# Interconnect_board_limit_switches_v1p5.net
KiCad netlist of a schematic drawn in EAGLE
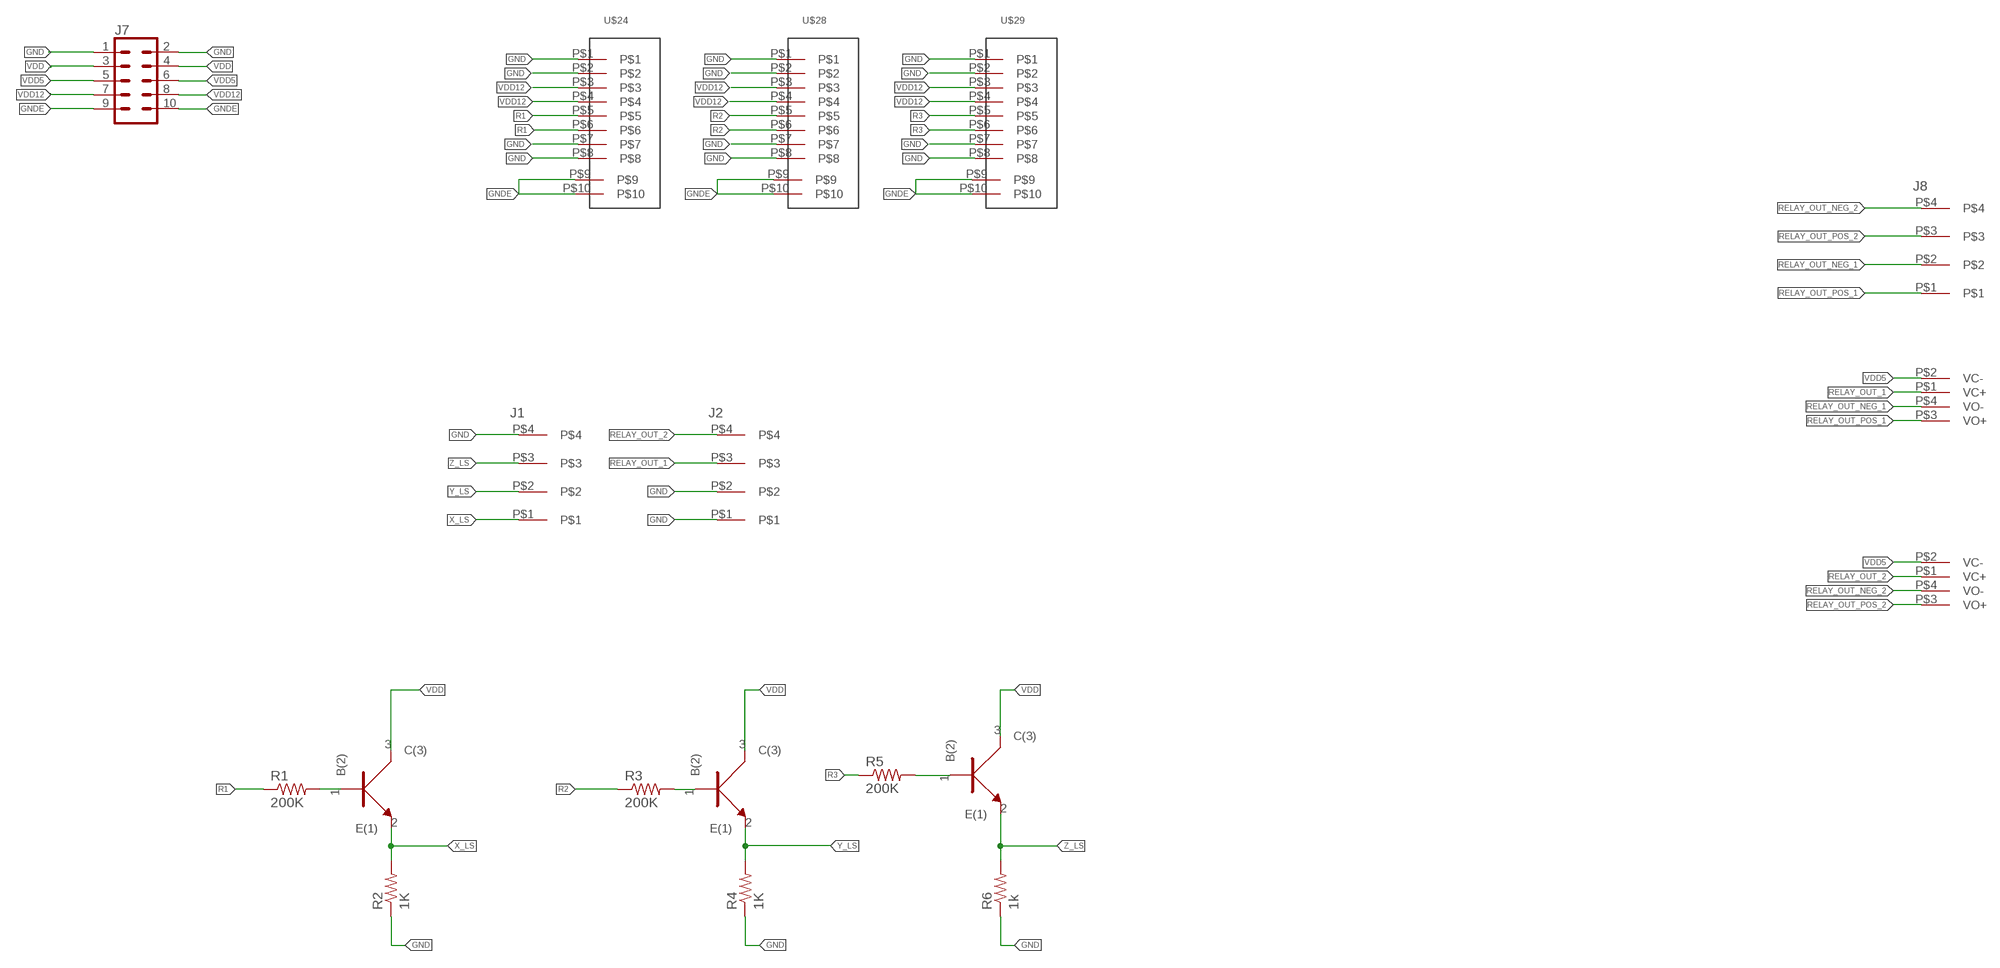
[diagram p0: schematic, sheet 1]

(export (version "E")
  (design (tool "Eeschema 10.0.6"))
  (components
    (comp (ref "J1")
      (value "3.81MM_1_X_4_RT_ANGLE_PLUG_HEADER")
      (footprint "eagle-import:1X4_3.81MM_PITCH")
      (libsource (lib "eagle-import") (part "3.81MM_1_X_4_RT_ANGLE_PLUG_HEADER"))
    )
    (comp (ref "J2")
      (value "3.81MM_1_X_4_RT_ANGLE_PLUG_HEADER")
      (footprint "eagle-import:1X4_3.81MM_PITCH")
      (libsource (lib "eagle-import") (part "3.81MM_1_X_4_RT_ANGLE_PLUG_HEADER"))
    )
    (comp (ref "J7")
      (value "CONN_05X2PTH")
      (footprint "eagle-import:2X5")
      (libsource (lib "eagle-import") (part "CONN_05X2PTH"))
    )
    (comp (ref "J8")
      (value "3.81MM_1_X_4_RT_ANGLE_PLUG_HEADER")
      (footprint "eagle-import:1X4_3.81MM_PITCH")
      (libsource (lib "eagle-import") (part "3.81MM_1_X_4_RT_ANGLE_PLUG_HEADER"))
    )
    (comp (ref "R1")
      (value "200K")
      (footprint "eagle-import:0805")
      (libsource (lib "eagle-import") (part "R_0805"))
    )
    (comp (ref "R2")
      (value "1K")
      (footprint "eagle-import:0805")
      (libsource (lib "eagle-import") (part "R_0805"))
    )
    (comp (ref "R3")
      (value "200K")
      (footprint "eagle-import:0805")
      (libsource (lib "eagle-import") (part "R_0805"))
    )
    (comp (ref "R4")
      (value "1K")
      (footprint "eagle-import:0805")
      (libsource (lib "eagle-import") (part "R_0805"))
    )
    (comp (ref "R5")
      (value "200K")
      (footprint "eagle-import:0805")
      (libsource (lib "eagle-import") (part "R_0805"))
    )
    (comp (ref "R6")
      (value "1k")
      (footprint "eagle-import:0805")
      (libsource (lib "eagle-import") (part "R_0805"))
    )
    (comp (ref "U$5")
      (value "RELAY_KYOTO_KF0604D")
      (footprint "eagle-import:RELAY_KYOTO_KF0604D")
      (libsource (lib "eagle-import") (part "RELAY_KYOTO_KF0604D"))
    )
    (comp (ref "U$13")
      (value "RELAY_KYOTO_KF0604D")
      (footprint "eagle-import:RELAY_KYOTO_KF0604D")
      (libsource (lib "eagle-import") (part "RELAY_KYOTO_KF0604D"))
    )
    (comp (ref "U$24")
      (value "RJ45_SMTRJ")
      (footprint "eagle-import:RJ45_SMT")
      (libsource (lib "eagle-import") (part "RJ45_SMTRJ"))
    )
    (comp (ref "U$28")
      (value "RJ45_SMTRJ")
      (footprint "eagle-import:RJ45_SMT")
      (libsource (lib "eagle-import") (part "RJ45_SMTRJ"))
    )
    (comp (ref "U$29")
      (value "RJ45_SMTRJ")
      (footprint "eagle-import:RJ45_SMT")
      (libsource (lib "eagle-import") (part "RJ45_SMTRJ"))
    )
    (comp (ref "U1")
      (value "BC846BW")
      (footprint "eagle-import:SOT323")
      (libsource (lib "eagle-import") (part "BC846BW"))
    )
    (comp (ref "U2")
      (value "BC846BW")
      (footprint "eagle-import:SOT323")
      (libsource (lib "eagle-import") (part "BC846BW"))
    )
    (comp (ref "U3")
      (value "BC846BW")
      (footprint "eagle-import:SOT323")
      (libsource (lib "eagle-import") (part "BC846BW"))
    )
  )
  (nets
    (net (code "1") (name "GND") (class "Default")
      (node (ref "J1") (pin "P$4") (pinfunction "P$4_P$4") (pintype "bidirectional"))
      (node (ref "J2") (pin "P$1") (pinfunction "P$1_P$1") (pintype "bidirectional"))
      (node (ref "J2") (pin "P$2") (pinfunction "P$2_P$2") (pintype "bidirectional"))
      (node (ref "J7") (pin "1") (pinfunction "1_1") (pintype "passive"))
      (node (ref "J7") (pin "2") (pinfunction "2_2") (pintype "passive"))
      (node (ref "R2") (pin "1") (pinfunction "1_1") (pintype "passive"))
      (node (ref "R4") (pin "1") (pinfunction "1_1") (pintype "passive"))
      (node (ref "R6") (pin "1") (pinfunction "1_1") (pintype "passive"))
      (node (ref "U$24") (pin "P$1") (pinfunction "P$1_P$1") (pintype "bidirectional"))
      (node (ref "U$24") (pin "P$2") (pinfunction "P$2_P$2") (pintype "bidirectional"))
      (node (ref "U$24") (pin "P$7") (pinfunction "P$7_P$7") (pintype "bidirectional"))
      (node (ref "U$24") (pin "P$8") (pinfunction "P$8_P$8") (pintype "bidirectional"))
      (node (ref "U$28") (pin "P$1") (pinfunction "P$1_P$1") (pintype "bidirectional"))
      (node (ref "U$28") (pin "P$2") (pinfunction "P$2_P$2") (pintype "bidirectional"))
      (node (ref "U$28") (pin "P$7") (pinfunction "P$7_P$7") (pintype "bidirectional"))
      (node (ref "U$28") (pin "P$8") (pinfunction "P$8_P$8") (pintype "bidirectional"))
      (node (ref "U$29") (pin "P$1") (pinfunction "P$1_P$1") (pintype "bidirectional"))
      (node (ref "U$29") (pin "P$2") (pinfunction "P$2_P$2") (pintype "bidirectional"))
      (node (ref "U$29") (pin "P$7") (pinfunction "P$7_P$7") (pintype "bidirectional"))
      (node (ref "U$29") (pin "P$8") (pinfunction "P$8_P$8") (pintype "bidirectional"))
    )
    (net (code "2") (name "GNDE") (class "Default")
      (node (ref "J7") (pin "10") (pinfunction "10_10") (pintype "passive"))
      (node (ref "J7") (pin "9") (pinfunction "9_9") (pintype "passive"))
      (node (ref "U$24") (pin "P$10") (pinfunction "P$10_P$10") (pintype "bidirectional"))
      (node (ref "U$24") (pin "P$9") (pinfunction "P$9_P$9") (pintype "bidirectional"))
      (node (ref "U$28") (pin "P$10") (pinfunction "P$10_P$10") (pintype "bidirectional"))
      (node (ref "U$28") (pin "P$9") (pinfunction "P$9_P$9") (pintype "bidirectional"))
      (node (ref "U$29") (pin "P$10") (pinfunction "P$10_P$10") (pintype "bidirectional"))
      (node (ref "U$29") (pin "P$9") (pinfunction "P$9_P$9") (pintype "bidirectional"))
    )
    (net (code "3") (name "Net-(U1-B(2))") (class "Default")
      (node (ref "R1") (pin "2") (pinfunction "2_2") (pintype "passive"))
      (node (ref "U1") (pin "1") (pinfunction "B(2)_1") (pintype "input"))
    )
    (net (code "4") (name "Net-(U2-B(2))") (class "Default")
      (node (ref "R3") (pin "2") (pinfunction "2_2") (pintype "passive"))
      (node (ref "U2") (pin "1") (pinfunction "B(2)_1") (pintype "input"))
    )
    (net (code "5") (name "Net-(U3-B(2))") (class "Default")
      (node (ref "R5") (pin "2") (pinfunction "2_2") (pintype "passive"))
      (node (ref "U3") (pin "1") (pinfunction "B(2)_1") (pintype "input"))
    )
    (net (code "6") (name "R1") (class "Default")
      (node (ref "R1") (pin "1") (pinfunction "1_1") (pintype "passive"))
      (node (ref "U$24") (pin "P$5") (pinfunction "P$5_P$5") (pintype "bidirectional"))
      (node (ref "U$24") (pin "P$6") (pinfunction "P$6_P$6") (pintype "bidirectional"))
    )
    (net (code "7") (name "R2") (class "Default")
      (node (ref "R3") (pin "1") (pinfunction "1_1") (pintype "passive"))
      (node (ref "U$28") (pin "P$5") (pinfunction "P$5_P$5") (pintype "bidirectional"))
      (node (ref "U$28") (pin "P$6") (pinfunction "P$6_P$6") (pintype "bidirectional"))
    )
    (net (code "8") (name "R3") (class "Default")
      (node (ref "R5") (pin "1") (pinfunction "1_1") (pintype "passive"))
      (node (ref "U$29") (pin "P$5") (pinfunction "P$5_P$5") (pintype "bidirectional"))
      (node (ref "U$29") (pin "P$6") (pinfunction "P$6_P$6") (pintype "bidirectional"))
    )
    (net (code "9") (name "RELAY_OUT_1") (class "Default")
      (node (ref "J2") (pin "P$3") (pinfunction "P$3_P$3") (pintype "bidirectional"))
      (node (ref "U$5") (pin "P$1") (pinfunction "VC+_P$1") (pintype "bidirectional"))
    )
    (net (code "10") (name "RELAY_OUT_2") (class "Default")
      (node (ref "J2") (pin "P$4") (pinfunction "P$4_P$4") (pintype "bidirectional"))
      (node (ref "U$13") (pin "P$1") (pinfunction "VC+_P$1") (pintype "bidirectional"))
    )
    (net (code "11") (name "RELAY_OUT_NEG_1") (class "Default")
      (node (ref "J8") (pin "P$2") (pinfunction "P$2_P$2") (pintype "bidirectional"))
      (node (ref "U$5") (pin "P$4") (pinfunction "VO-_P$4") (pintype "bidirectional"))
    )
    (net (code "12") (name "RELAY_OUT_NEG_2") (class "Default")
      (node (ref "J8") (pin "P$4") (pinfunction "P$4_P$4") (pintype "bidirectional"))
      (node (ref "U$13") (pin "P$4") (pinfunction "VO-_P$4") (pintype "bidirectional"))
    )
    (net (code "13") (name "RELAY_OUT_POS_1") (class "Default")
      (node (ref "J8") (pin "P$1") (pinfunction "P$1_P$1") (pintype "bidirectional"))
      (node (ref "U$5") (pin "P$3") (pinfunction "VO+_P$3") (pintype "bidirectional"))
    )
    (net (code "14") (name "RELAY_OUT_POS_2") (class "Default")
      (node (ref "J8") (pin "P$3") (pinfunction "P$3_P$3") (pintype "bidirectional"))
      (node (ref "U$13") (pin "P$3") (pinfunction "VO+_P$3") (pintype "bidirectional"))
    )
    (net (code "15") (name "VDD") (class "Default")
      (node (ref "J7") (pin "3") (pinfunction "3_3") (pintype "passive"))
      (node (ref "J7") (pin "4") (pinfunction "4_4") (pintype "passive"))
      (node (ref "U1") (pin "3") (pinfunction "C(3)_3") (pintype "input"))
      (node (ref "U2") (pin "3") (pinfunction "C(3)_3") (pintype "input"))
      (node (ref "U3") (pin "3") (pinfunction "C(3)_3") (pintype "input"))
    )
    (net (code "16") (name "VDD5") (class "Default")
      (node (ref "J7") (pin "5") (pinfunction "5_5") (pintype "passive"))
      (node (ref "J7") (pin "6") (pinfunction "6_6") (pintype "passive"))
      (node (ref "U$13") (pin "P$2") (pinfunction "VC-_P$2") (pintype "bidirectional"))
      (node (ref "U$5") (pin "P$2") (pinfunction "VC-_P$2") (pintype "bidirectional"))
    )
    (net (code "17") (name "VDD12") (class "Default")
      (node (ref "J7") (pin "7") (pinfunction "7_7") (pintype "passive"))
      (node (ref "J7") (pin "8") (pinfunction "8_8") (pintype "passive"))
      (node (ref "U$24") (pin "P$3") (pinfunction "P$3_P$3") (pintype "bidirectional"))
      (node (ref "U$24") (pin "P$4") (pinfunction "P$4_P$4") (pintype "bidirectional"))
      (node (ref "U$28") (pin "P$3") (pinfunction "P$3_P$3") (pintype "bidirectional"))
      (node (ref "U$28") (pin "P$4") (pinfunction "P$4_P$4") (pintype "bidirectional"))
      (node (ref "U$29") (pin "P$3") (pinfunction "P$3_P$3") (pintype "bidirectional"))
      (node (ref "U$29") (pin "P$4") (pinfunction "P$4_P$4") (pintype "bidirectional"))
    )
    (net (code "18") (name "X_LS") (class "Default")
      (node (ref "J1") (pin "P$1") (pinfunction "P$1_P$1") (pintype "bidirectional"))
      (node (ref "R2") (pin "2") (pinfunction "2_2") (pintype "passive"))
      (node (ref "U1") (pin "2") (pinfunction "E(1)_2") (pintype "output"))
    )
    (net (code "19") (name "Y_LS") (class "Default")
      (node (ref "J1") (pin "P$2") (pinfunction "P$2_P$2") (pintype "bidirectional"))
      (node (ref "R4") (pin "2") (pinfunction "2_2") (pintype "passive"))
      (node (ref "U2") (pin "2") (pinfunction "E(1)_2") (pintype "output"))
    )
    (net (code "20") (name "Z_LS") (class "Default")
      (node (ref "J1") (pin "P$3") (pinfunction "P$3_P$3") (pintype "bidirectional"))
      (node (ref "R6") (pin "2") (pinfunction "2_2") (pintype "passive"))
      (node (ref "U3") (pin "2") (pinfunction "E(1)_2") (pintype "output"))
    )
  )
)
